# PCB.net
KiCad netlist of a schematic drawn in EasyEDA Pro
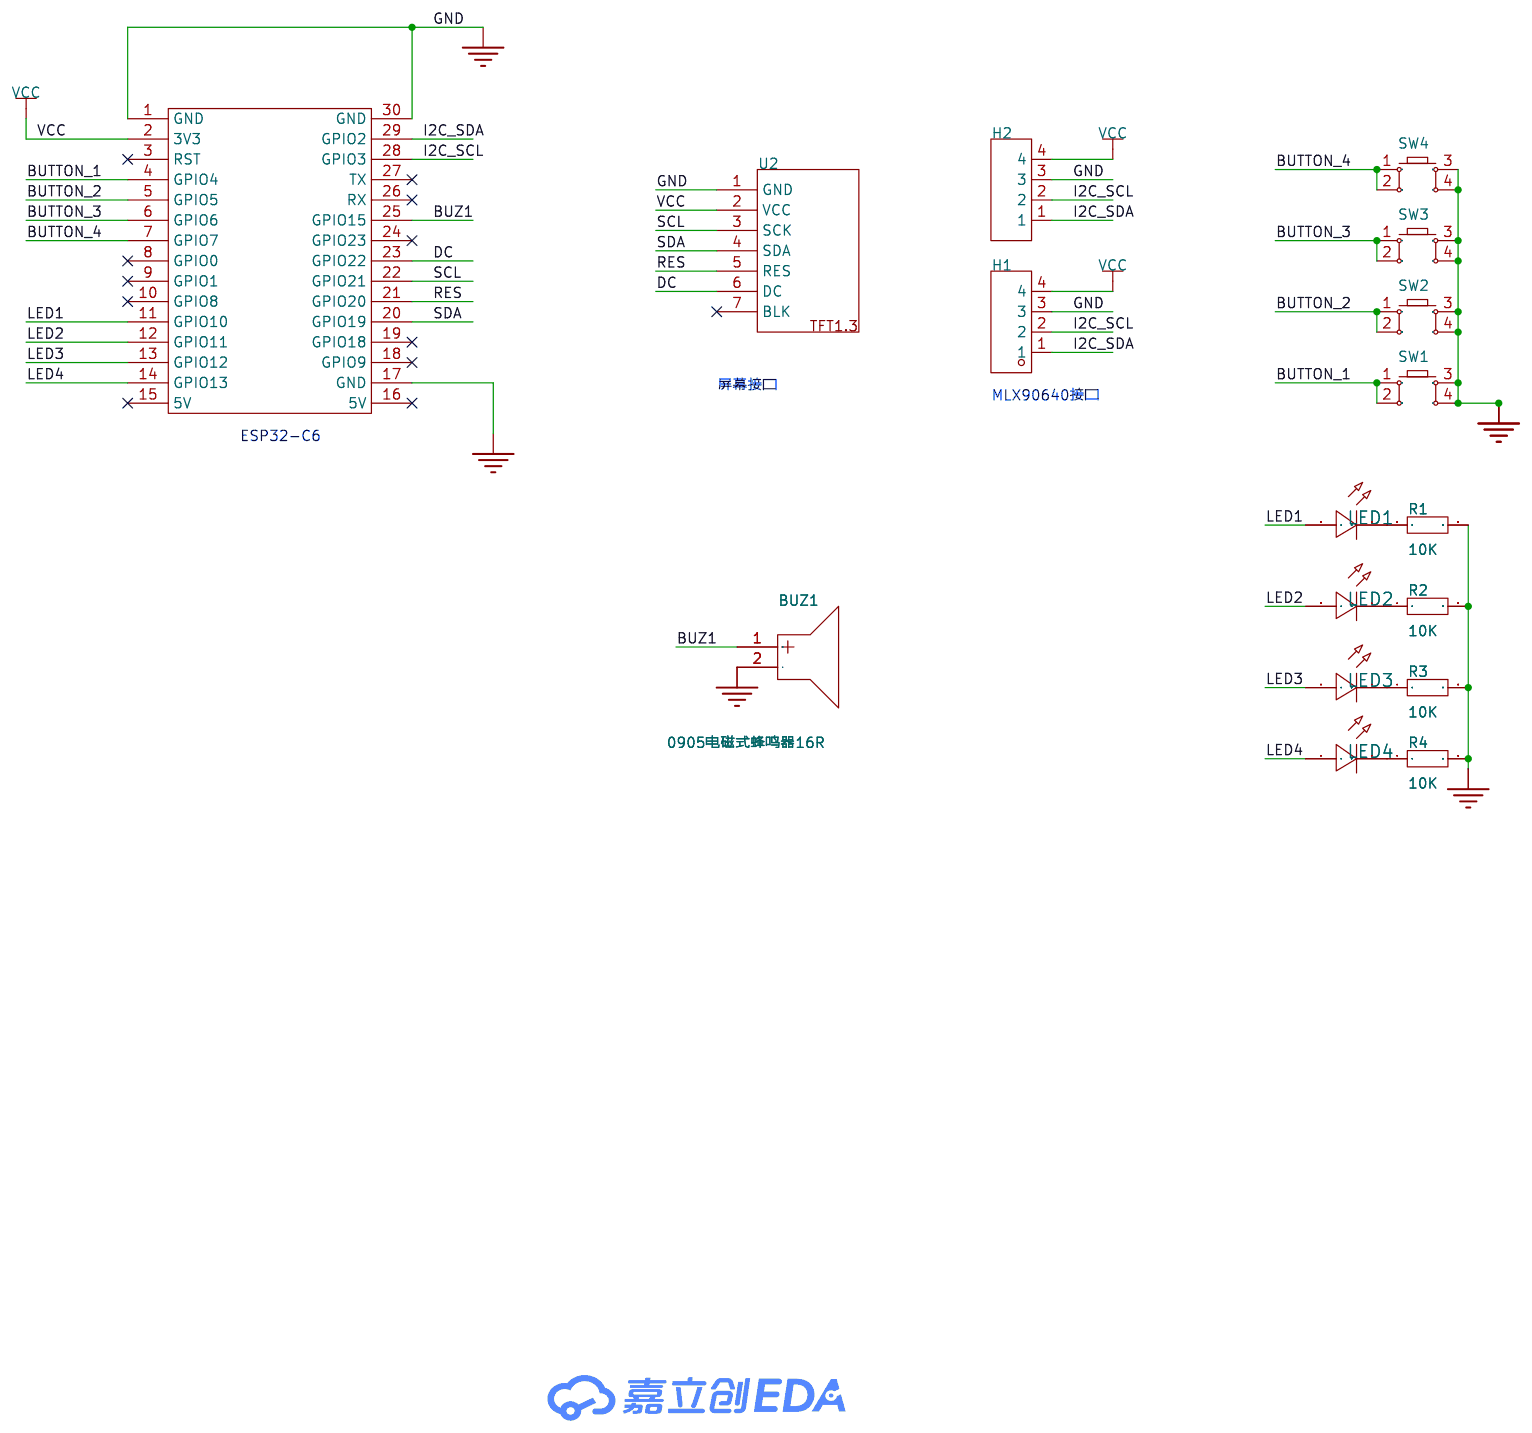
[diagram p0: schematic sheet]

(export (version "E")
  (design (tool "Eeschema 10.0.6"))
  (components
    (comp (ref "BUZ1")
      (value "0905电磁式蜂鸣器16R")
      (footprint "easyedapro:BUZ-TH_BD9.0-P4.00-D0.6-FD")
      (libsource (lib "easyedapro") (part "0905电磁式蜂鸣器16R"))
    )
    (comp (ref "H1")
      (value "~")
      (footprint "easyedapro:HDR-TH_4P-P2.54-V-F")
      (libsource (lib "easyedapro") (part "2.54-1*4P母"))
    )
    (comp (ref "H2")
      (value "~")
      (footprint "easyedapro:HDR-TH_4P-P2.54-V-M")
      (libsource (lib "easyedapro") (part "PZ254V-11-04P"))
    )
    (comp (ref "LED1")
      (value "~")
      (footprint "easyedapro:LED_0603")
      (libsource (lib "easyedapro") (part "LED_R"))
    )
    (comp (ref "LED2")
      (value "~")
      (footprint "easyedapro:LED_0603")
      (libsource (lib "easyedapro") (part "LED_R"))
    )
    (comp (ref "LED3")
      (value "~")
      (footprint "easyedapro:LED_0603")
      (libsource (lib "easyedapro") (part "LED_R"))
    )
    (comp (ref "LED4")
      (value "~")
      (footprint "easyedapro:LED_0603")
      (libsource (lib "easyedapro") (part "LED_R"))
    )
    (comp (ref "R1") (value "10K") (footprint "easyedapro:R0603") (libsource (lib "easyedapro") (part "电阻")))
    (comp (ref "R2") (value "10K") (footprint "easyedapro:R0603") (libsource (lib "easyedapro") (part "电阻")))
    (comp (ref "R3") (value "10K") (footprint "easyedapro:R0603") (libsource (lib "easyedapro") (part "电阻")))
    (comp (ref "R4") (value "10K") (footprint "easyedapro:R0603") (libsource (lib "easyedapro") (part "电阻")))
    (comp (ref "SW1")
      (value "~")
      (footprint "easyedapro:SW-SMD_4P-L6.0-W6.0-P4.50-LS9.0-2")
      (libsource (lib "easyedapro") (part "轻触按键"))
    )
    (comp (ref "SW2")
      (value "~")
      (footprint "easyedapro:SW-SMD_4P-L6.0-W6.0-P4.50-LS9.0-2")
      (libsource (lib "easyedapro") (part "轻触按键"))
    )
    (comp (ref "SW3")
      (value "~")
      (footprint "easyedapro:SW-SMD_4P-L6.0-W6.0-P4.50-LS9.0-2")
      (libsource (lib "easyedapro") (part "轻触按键"))
    )
    (comp (ref "SW4")
      (value "~")
      (footprint "easyedapro:SW-SMD_4P-L6.0-W6.0-P4.50-LS9.0-2")
      (libsource (lib "easyedapro") (part "轻触按键"))
    )
    (comp (ref "U2")
      (value "~")
      (footprint "easyedapro:tft1.3寸")
      (libsource (lib "easyedapro") (part "tft1.3寸"))
    )
    (comp (ref "U3")
      (value "~")
      (footprint "easyedapro:ESP32-C6-开发板")
      (libsource (lib "easyedapro") (part "ESP32-C6-开发板"))
    )
  )
  (nets
    (net (code "1") (name "/BUTTON_1") (class "Default")
      (node (ref "SW1") (pin "1") (pinfunction "1_1") (pintype "input"))
      (node (ref "SW1") (pin "2") (pinfunction "2_2") (pintype "input"))
      (node (ref "U3") (pin "4") (pinfunction "GPIO4_4") (pintype "input"))
    )
    (net (code "2") (name "/BUTTON_2") (class "Default")
      (node (ref "SW2") (pin "1") (pinfunction "1_1") (pintype "input"))
      (node (ref "SW2") (pin "2") (pinfunction "2_2") (pintype "input"))
      (node (ref "U3") (pin "5") (pinfunction "GPIO5_5") (pintype "input"))
    )
    (net (code "3") (name "/BUTTON_3") (class "Default")
      (node (ref "SW3") (pin "1") (pinfunction "1_1") (pintype "input"))
      (node (ref "SW3") (pin "2") (pinfunction "2_2") (pintype "input"))
      (node (ref "U3") (pin "6") (pinfunction "GPIO6_6") (pintype "input"))
    )
    (net (code "4") (name "/BUTTON_4") (class "Default")
      (node (ref "SW4") (pin "1") (pinfunction "1_1") (pintype "input"))
      (node (ref "SW4") (pin "2") (pinfunction "2_2") (pintype "input"))
      (node (ref "U3") (pin "7") (pinfunction "GPIO7_7") (pintype "input"))
    )
    (net (code "5") (name "/BUZ1") (class "Default")
      (node (ref "BUZ1") (pin "1") (pinfunction "+_1") (pintype "unspecified"))
      (node (ref "U3") (pin "25") (pinfunction "GPIO15_25") (pintype "input"))
    )
    (net (code "6") (name "/DC") (class "Default")
      (node (ref "U2") (pin "6") (pinfunction "DC_6") (pintype "input"))
      (node (ref "U3") (pin "23") (pinfunction "GPIO22_23") (pintype "input"))
    )
    (net (code "7") (name "/I2C_SCL") (class "Default")
      (node (ref "H1") (pin "2") (pinfunction "2_2") (pintype "unspecified"))
      (node (ref "H2") (pin "2") (pinfunction "2_2") (pintype "unspecified"))
      (node (ref "U3") (pin "28") (pinfunction "GPIO3_28") (pintype "input"))
    )
    (net (code "8") (name "/I2C_SDA") (class "Default")
      (node (ref "H1") (pin "1") (pinfunction "1_1") (pintype "unspecified"))
      (node (ref "H2") (pin "1") (pinfunction "1_1") (pintype "unspecified"))
      (node (ref "U3") (pin "29") (pinfunction "GPIO2_29") (pintype "input"))
    )
    (net (code "9") (name "/LED1") (class "Default")
      (node (ref "LED1") (pin "2") (pinfunction "A_2") (pintype "input"))
      (node (ref "U3") (pin "11") (pinfunction "GPIO10_11") (pintype "input"))
    )
    (net (code "10") (name "/LED2") (class "Default")
      (node (ref "LED2") (pin "2") (pinfunction "A_2") (pintype "input"))
      (node (ref "U3") (pin "12") (pinfunction "GPIO11_12") (pintype "input"))
    )
    (net (code "11") (name "/LED3") (class "Default")
      (node (ref "LED3") (pin "2") (pinfunction "A_2") (pintype "input"))
      (node (ref "U3") (pin "13") (pinfunction "GPIO12_13") (pintype "input"))
    )
    (net (code "12") (name "/LED4") (class "Default")
      (node (ref "LED4") (pin "2") (pinfunction "A_2") (pintype "input"))
      (node (ref "U3") (pin "14") (pinfunction "GPIO13_14") (pintype "input"))
    )
    (net (code "13") (name "/RES") (class "Default")
      (node (ref "U2") (pin "5") (pinfunction "RES_5") (pintype "input"))
      (node (ref "U3") (pin "21") (pinfunction "GPIO20_21") (pintype "input"))
    )
    (net (code "14") (name "/SCL") (class "Default")
      (node (ref "U2") (pin "3") (pinfunction "SCK_3") (pintype "input"))
      (node (ref "U3") (pin "22") (pinfunction "GPIO21_22") (pintype "input"))
    )
    (net (code "15") (name "/SDA") (class "Default")
      (node (ref "U2") (pin "4") (pinfunction "SDA_4") (pintype "input"))
      (node (ref "U3") (pin "20") (pinfunction "GPIO19_20") (pintype "input"))
    )
    (net (code "16") (name "GND") (class "Default")
      (node (ref "BUZ1") (pin "2") (pinfunction "-_2") (pintype "unspecified"))
      (node (ref "H1") (pin "3") (pinfunction "3_3") (pintype "unspecified"))
      (node (ref "H2") (pin "3") (pinfunction "3_3") (pintype "unspecified"))
      (node (ref "R1") (pin "2") (pinfunction "2_2") (pintype "input"))
      (node (ref "R2") (pin "2") (pinfunction "2_2") (pintype "input"))
      (node (ref "R3") (pin "2") (pinfunction "2_2") (pintype "input"))
      (node (ref "R4") (pin "2") (pinfunction "2_2") (pintype "input"))
      (node (ref "SW1") (pin "3") (pinfunction "3_3") (pintype "input"))
      (node (ref "SW1") (pin "4") (pinfunction "4_4") (pintype "input"))
      (node (ref "SW2") (pin "3") (pinfunction "3_3") (pintype "input"))
      (node (ref "SW2") (pin "4") (pinfunction "4_4") (pintype "input"))
      (node (ref "SW3") (pin "3") (pinfunction "3_3") (pintype "input"))
      (node (ref "SW3") (pin "4") (pinfunction "4_4") (pintype "input"))
      (node (ref "SW4") (pin "3") (pinfunction "3_3") (pintype "input"))
      (node (ref "SW4") (pin "4") (pinfunction "4_4") (pintype "input"))
      (node (ref "U2") (pin "1") (pinfunction "GND_1") (pintype "input"))
      (node (ref "U3") (pin "1") (pinfunction "GND_1") (pintype "input"))
      (node (ref "U3") (pin "17") (pinfunction "GND_17") (pintype "input"))
      (node (ref "U3") (pin "30") (pinfunction "GND_30") (pintype "input"))
    )
    (net (code "17") (name "Net-(LED1-C)") (class "Default")
      (node (ref "LED1") (pin "1") (pinfunction "C_1") (pintype "input"))
      (node (ref "R1") (pin "1") (pinfunction "1_1") (pintype "input"))
    )
    (net (code "18") (name "Net-(LED2-C)") (class "Default")
      (node (ref "LED2") (pin "1") (pinfunction "C_1") (pintype "input"))
      (node (ref "R2") (pin "1") (pinfunction "1_1") (pintype "input"))
    )
    (net (code "19") (name "Net-(LED3-C)") (class "Default")
      (node (ref "LED3") (pin "1") (pinfunction "C_1") (pintype "input"))
      (node (ref "R3") (pin "1") (pinfunction "1_1") (pintype "input"))
    )
    (net (code "20") (name "Net-(LED4-C)") (class "Default")
      (node (ref "LED4") (pin "1") (pinfunction "C_1") (pintype "input"))
      (node (ref "R4") (pin "1") (pinfunction "1_1") (pintype "input"))
    )
    (net (code "21") (name "VCC") (class "Default")
      (node (ref "H1") (pin "4") (pinfunction "4_4") (pintype "unspecified"))
      (node (ref "H2") (pin "4") (pinfunction "4_4") (pintype "unspecified"))
      (node (ref "U2") (pin "2") (pinfunction "VCC_2") (pintype "input"))
      (node (ref "U3") (pin "2") (pinfunction "3V3_2") (pintype "input"))
    )
    (net (code "22") (name "unconnected-(U2-BLK-Pad7)") (class "Default")
      (node (ref "U2") (pin "7") (pinfunction "BLK_7") (pintype "input+no_connect"))
    )
    (net (code "23") (name "unconnected-(U3-5V-Pad15)") (class "Default")
      (node (ref "U3") (pin "15") (pinfunction "5V_15") (pintype "input+no_connect"))
    )
    (net (code "24") (name "unconnected-(U3-5V-Pad16)") (class "Default")
      (node (ref "U3") (pin "16") (pinfunction "5V_16") (pintype "input+no_connect"))
    )
    (net (code "25") (name "unconnected-(U3-GPIO0-Pad8)") (class "Default")
      (node (ref "U3") (pin "8") (pinfunction "GPIO0_8") (pintype "input+no_connect"))
    )
    (net (code "26") (name "unconnected-(U3-GPIO1-Pad9)") (class "Default")
      (node (ref "U3") (pin "9") (pinfunction "GPIO1_9") (pintype "input+no_connect"))
    )
    (net (code "27") (name "unconnected-(U3-GPIO8-Pad10)") (class "Default")
      (node (ref "U3") (pin "10") (pinfunction "GPIO8_10") (pintype "input+no_connect"))
    )
    (net (code "28") (name "unconnected-(U3-GPIO9-Pad18)") (class "Default")
      (node (ref "U3") (pin "18") (pinfunction "GPIO9_18") (pintype "input+no_connect"))
    )
    (net (code "29") (name "unconnected-(U3-GPIO18-Pad19)") (class "Default")
      (node (ref "U3") (pin "19") (pinfunction "GPIO18_19") (pintype "input+no_connect"))
    )
    (net (code "30") (name "unconnected-(U3-GPIO23-Pad24)") (class "Default")
      (node (ref "U3") (pin "24") (pinfunction "GPIO23_24") (pintype "input+no_connect"))
    )
    (net (code "31") (name "unconnected-(U3-RST-Pad3)") (class "Default")
      (node (ref "U3") (pin "3") (pinfunction "RST_3") (pintype "input+no_connect"))
    )
    (net (code "32") (name "unconnected-(U3-RX-Pad26)") (class "Default")
      (node (ref "U3") (pin "26") (pinfunction "RX_26") (pintype "input+no_connect"))
    )
    (net (code "33") (name "unconnected-(U3-TX-Pad27)") (class "Default")
      (node (ref "U3") (pin "27") (pinfunction "TX_27") (pintype "input+no_connect"))
    )
  )
)
